# 11_Camera_Input.net
KiCad netlist of a schematic drawn in Altium Designer
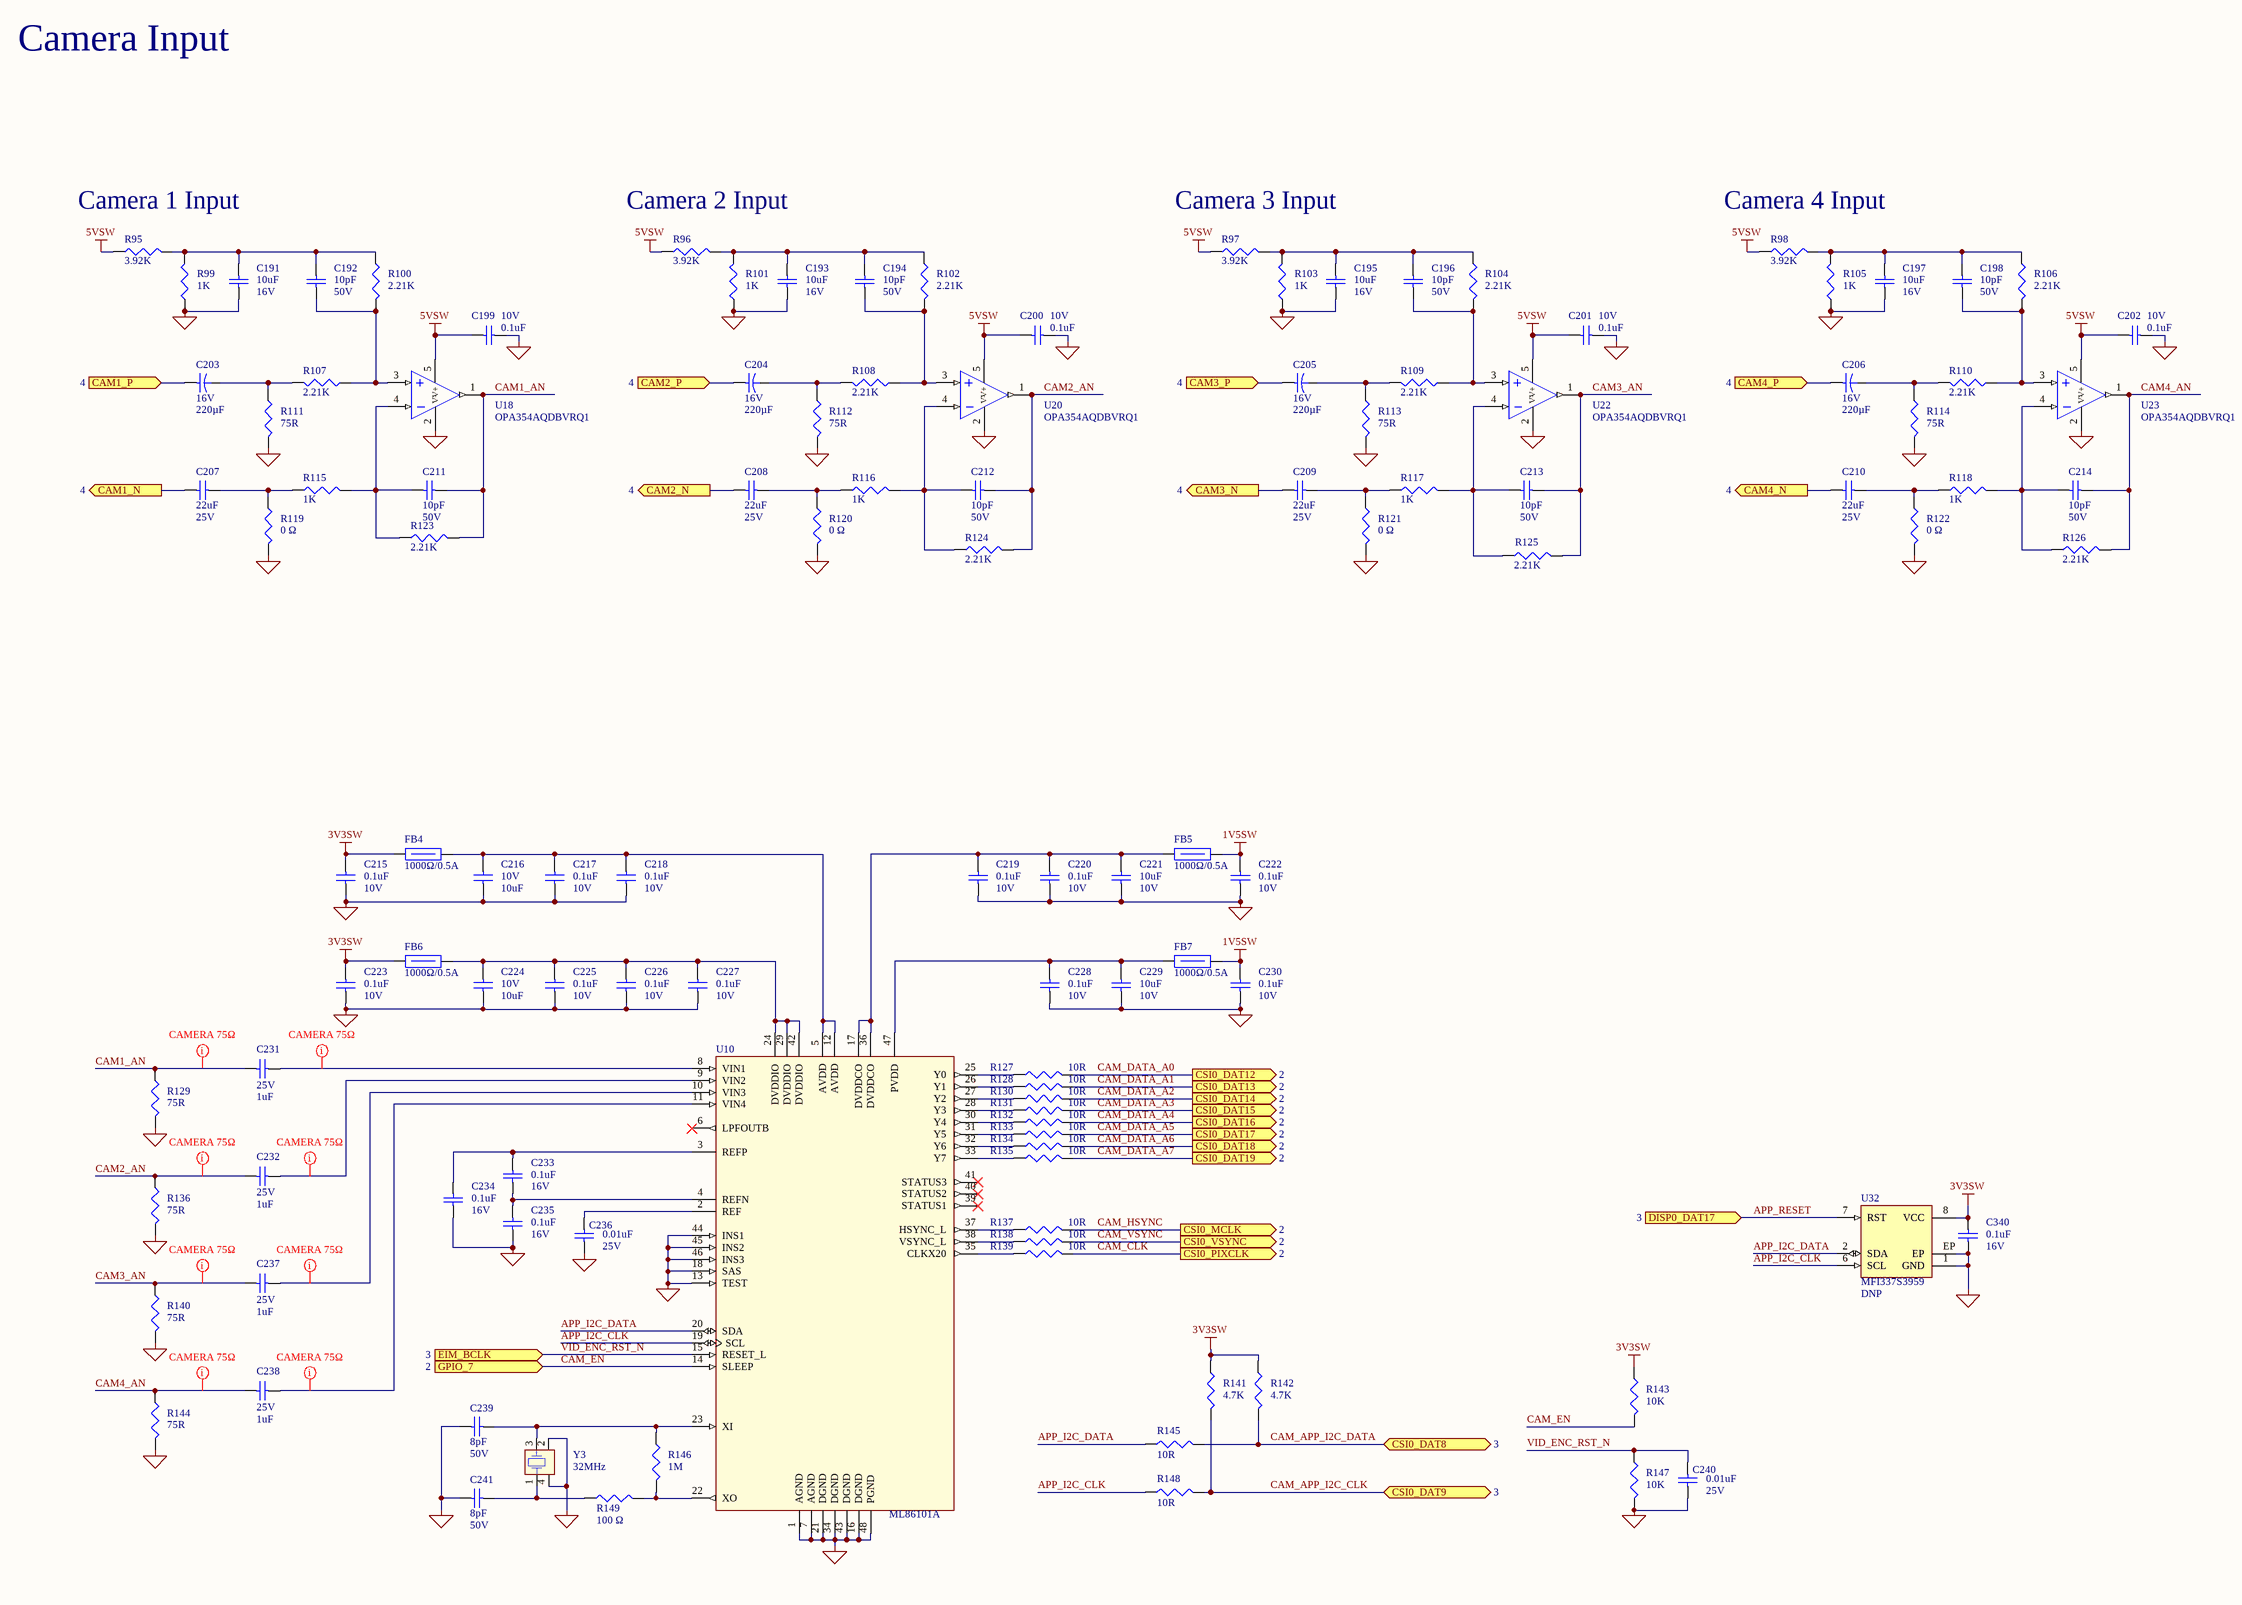
[diagram p0: 11 Camera Input.SchDoc]

(export (version "E")
  (design (tool "Eeschema 10.0.6"))
  (components
    (comp (ref "C191")
      (value "10uF")
      (footprint "CAP_0603")
      (description "Cap, Cer, 10uF, 16V, 20%, X5R, 0603")
      (fields
        (field (name "TOLERANCE") "±20%")
        (field (name "MANUFACTURER") "Murata Electronics North America")
        (field (name "VOLTAGE") "16V")
      )
      (libsource (lib "Firstview") (part "Cap 10uF 16V 0603"))
    )
    (comp (ref "C192")
      (value "10pF")
      (footprint "CAP_0402")
      (description "Cap, Cer, 10pF, 50V, 5%, C0G/NP0, 0402")
      (fields
        (field (name "TOLERANCE") "5%")
        (field (name "MANUFACTURER") "Yageo")
        (field (name "VOLTAGE") "50V")
      )
      (libsource (lib "Firstview") (part "Cap 10pF 50V 0402"))
    )
    (comp (ref "C193")
      (value "10uF")
      (footprint "CAP_0603")
      (description "Cap, Cer, 10uF, 16V, 20%, X5R, 0603")
      (fields
        (field (name "TOLERANCE") "±20%")
        (field (name "MANUFACTURER") "Murata Electronics North America")
        (field (name "VOLTAGE") "16V")
      )
      (libsource (lib "Firstview") (part "Cap 10uF 16V 0603"))
    )
    (comp (ref "C194")
      (value "10pF")
      (footprint "CAP_0402")
      (description "Cap, Cer, 10pF, 50V, 5%, C0G/NP0, 0402")
      (fields
        (field (name "TOLERANCE") "5%")
        (field (name "MANUFACTURER") "Yageo")
        (field (name "VOLTAGE") "50V")
      )
      (libsource (lib "Firstview") (part "Cap 10pF 50V 0402"))
    )
    (comp (ref "C195")
      (value "10uF")
      (footprint "CAP_0603")
      (description "Cap, Cer, 10uF, 16V, 20%, X5R, 0603")
      (fields
        (field (name "TOLERANCE") "±20%")
        (field (name "MANUFACTURER") "Murata Electronics North America")
        (field (name "VOLTAGE") "16V")
      )
      (libsource (lib "Firstview") (part "Cap 10uF 16V 0603"))
    )
    (comp (ref "C196")
      (value "10pF")
      (footprint "CAP_0402")
      (description "Cap, Cer, 10pF, 50V, 5%, C0G/NP0, 0402")
      (fields
        (field (name "TOLERANCE") "5%")
        (field (name "MANUFACTURER") "Yageo")
        (field (name "VOLTAGE") "50V")
      )
      (libsource (lib "Firstview") (part "Cap 10pF 50V 0402"))
    )
    (comp (ref "C197")
      (value "10uF")
      (footprint "CAP_0603")
      (description "Cap, Cer, 10uF, 16V, 20%, X5R, 0603")
      (fields
        (field (name "TOLERANCE") "±20%")
        (field (name "MANUFACTURER") "Murata Electronics North America")
        (field (name "VOLTAGE") "16V")
      )
      (libsource (lib "Firstview") (part "Cap 10uF 16V 0603"))
    )
    (comp (ref "C198")
      (value "10pF")
      (footprint "CAP_0402")
      (description "Cap, Cer, 10pF, 50V, 5%, C0G/NP0, 0402")
      (fields
        (field (name "TOLERANCE") "5%")
        (field (name "MANUFACTURER") "Yageo")
        (field (name "VOLTAGE") "50V")
      )
      (libsource (lib "Firstview") (part "Cap 10pF 50V 0402"))
    )
    (comp (ref "C199")
      (value "0.1uF")
      (footprint "CAP_0402")
      (description "Cap, Cer, 0.1uF, 10V, 10%, X5R, 0402")
      (fields
        (field (name "TOLERANCE") "±10%")
        (field (name "MANUFACTURER") "Murata Electronics North America")
        (field (name "VOLTAGE") "10V")
      )
      (libsource (lib "Firstview") (part "Cap 0.1uF 10V 0402"))
    )
    (comp (ref "C200")
      (value "0.1uF")
      (footprint "CAP_0402")
      (description "Cap, Cer, 0.1uF, 10V, 10%, X5R, 0402")
      (fields
        (field (name "TOLERANCE") "±10%")
        (field (name "MANUFACTURER") "Murata Electronics North America")
        (field (name "VOLTAGE") "10V")
      )
      (libsource (lib "Firstview") (part "Cap 0.1uF 10V 0402"))
    )
    (comp (ref "C201")
      (value "0.1uF")
      (footprint "CAP_0402")
      (description "Cap, Cer, 0.1uF, 10V, 10%, X5R, 0402")
      (fields
        (field (name "TOLERANCE") "±10%")
        (field (name "MANUFACTURER") "Murata Electronics North America")
        (field (name "VOLTAGE") "10V")
      )
      (libsource (lib "Firstview") (part "Cap 0.1uF 10V 0402"))
    )
    (comp (ref "C202")
      (value "0.1uF")
      (footprint "CAP_0402")
      (description "Cap, Cer, 0.1uF, 10V, 10%, X5R, 0402")
      (fields
        (field (name "TOLERANCE") "±10%")
        (field (name "MANUFACTURER") "Murata Electronics North America")
        (field (name "VOLTAGE") "10V")
      )
      (libsource (lib "Firstview") (part "Cap 0.1uF 10V 0402"))
    )
    (comp (ref "C203")
      (value "220µF")
      (footprint "SMD(6.6x6.6)_UWT1C221MCL1GS")
      (description "Cap, Alum, 220µF, 16V, 20%, SMD")
      (fields
        (field (name "TOLERANCE") "20%")
        (field (name "MANUFACTURER") "Nichicon")
        (field (name "VOLTAGE") "16V")
      )
      (libsource (lib "Firstview") (part "Cap 220µF 16V"))
    )
    (comp (ref "C204")
      (value "220µF")
      (footprint "SMD(6.6x6.6)_UWT1C221MCL1GS")
      (description "Cap, Alum, 220µF, 16V, 20%, SMD")
      (fields
        (field (name "TOLERANCE") "20%")
        (field (name "MANUFACTURER") "Nichicon")
        (field (name "VOLTAGE") "16V")
      )
      (libsource (lib "Firstview") (part "Cap 220µF 16V"))
    )
    (comp (ref "C205")
      (value "220µF")
      (footprint "SMD(6.6x6.6)_UWT1C221MCL1GS")
      (description "Cap, Alum, 220µF, 16V, 20%, SMD")
      (fields
        (field (name "TOLERANCE") "20%")
        (field (name "MANUFACTURER") "Nichicon")
        (field (name "VOLTAGE") "16V")
      )
      (libsource (lib "Firstview") (part "Cap 220µF 16V"))
    )
    (comp (ref "C206")
      (value "220µF")
      (footprint "SMD(6.6x6.6)_UWT1C221MCL1GS")
      (description "Cap, Alum, 220µF, 16V, 20%, SMD")
      (fields
        (field (name "TOLERANCE") "20%")
        (field (name "MANUFACTURER") "Nichicon")
        (field (name "VOLTAGE") "16V")
      )
      (libsource (lib "Firstview") (part "Cap 220µF 16V"))
    )
    (comp (ref "C207")
      (value "22uF")
      (footprint "CAP_0805")
      (description "Cap, Cer, 22uF, 25V, 20%, X5R, 0805")
      (fields
        (field (name "TOLERANCE") "±20%")
        (field (name "MANUFACTURER") "Samsung Electro-Mechanics America, Inc")
        (field (name "VOLTAGE") "25V")
      )
      (libsource (lib "Firstview") (part "Cap 22uF 25V 0805"))
    )
    (comp (ref "C208")
      (value "22uF")
      (footprint "CAP_0805")
      (description "Cap, Cer, 22uF, 25V, 20%, X5R, 0805")
      (fields
        (field (name "TOLERANCE") "±20%")
        (field (name "MANUFACTURER") "Samsung Electro-Mechanics America, Inc")
        (field (name "VOLTAGE") "25V")
      )
      (libsource (lib "Firstview") (part "Cap 22uF 25V 0805"))
    )
    (comp (ref "C209")
      (value "22uF")
      (footprint "CAP_0805")
      (description "Cap, Cer, 22uF, 25V, 20%, X5R, 0805")
      (fields
        (field (name "TOLERANCE") "±20%")
        (field (name "MANUFACTURER") "Samsung Electro-Mechanics America, Inc")
        (field (name "VOLTAGE") "25V")
      )
      (libsource (lib "Firstview") (part "Cap 22uF 25V 0805"))
    )
    (comp (ref "C210")
      (value "22uF")
      (footprint "CAP_0805")
      (description "Cap, Cer, 22uF, 25V, 20%, X5R, 0805")
      (fields
        (field (name "TOLERANCE") "±20%")
        (field (name "MANUFACTURER") "Samsung Electro-Mechanics America, Inc")
        (field (name "VOLTAGE") "25V")
      )
      (libsource (lib "Firstview") (part "Cap 22uF 25V 0805"))
    )
    (comp (ref "C211")
      (value "10pF")
      (footprint "CAP_0402")
      (description "Cap, Cer, 10pF, 50V, 5%, C0G/NP0, 0402")
      (fields
        (field (name "TOLERANCE") "5%")
        (field (name "MANUFACTURER") "Yageo")
        (field (name "VOLTAGE") "50V")
      )
      (libsource (lib "Firstview") (part "Cap 10pF 50V 0402"))
    )
    (comp (ref "C212")
      (value "10pF")
      (footprint "CAP_0402")
      (description "Cap, Cer, 10pF, 50V, 5%, C0G/NP0, 0402")
      (fields
        (field (name "TOLERANCE") "5%")
        (field (name "MANUFACTURER") "Yageo")
        (field (name "VOLTAGE") "50V")
      )
      (libsource (lib "Firstview") (part "Cap 10pF 50V 0402"))
    )
    (comp (ref "C213")
      (value "10pF")
      (footprint "CAP_0402")
      (description "Cap, Cer, 10pF, 50V, 5%, C0G/NP0, 0402")
      (fields
        (field (name "TOLERANCE") "5%")
        (field (name "MANUFACTURER") "Yageo")
        (field (name "VOLTAGE") "50V")
      )
      (libsource (lib "Firstview") (part "Cap 10pF 50V 0402"))
    )
    (comp (ref "C214")
      (value "10pF")
      (footprint "CAP_0402")
      (description "Cap, Cer, 10pF, 50V, 5%, C0G/NP0, 0402")
      (fields
        (field (name "TOLERANCE") "5%")
        (field (name "MANUFACTURER") "Yageo")
        (field (name "VOLTAGE") "50V")
      )
      (libsource (lib "Firstview") (part "Cap 10pF 50V 0402"))
    )
    (comp (ref "C215")
      (value "0.1uF")
      (footprint "CAP_0402")
      (description "Cap, Cer, 0.1uF, 10V, 10%, X5R, 0402")
      (fields
        (field (name "TOLERANCE") "±10%")
        (field (name "MANUFACTURER") "Murata Electronics North America")
        (field (name "VOLTAGE") "10V")
      )
      (libsource (lib "Firstview") (part "Cap 0.1uF 10V 0402"))
    )
    (comp (ref "C216")
      (value "10uF")
      (footprint "CAP_0603")
      (description "Cap, Cer, 10uF, 10V, 10%, X5R, 0603")
      (fields
        (field (name "TOLERANCE") "±10%")
        (field (name "VOLTAGE") "10V")
        (field (name "MANUFACTURER") "TDK Corporation")
      )
      (libsource (lib "Firstview") (part "Cap 10uF 10V 0603"))
    )
    (comp (ref "C217")
      (value "0.1uF")
      (footprint "CAP_0402")
      (description "Cap, Cer, 0.1uF, 10V, 10%, X5R, 0402")
      (fields
        (field (name "TOLERANCE") "±10%")
        (field (name "MANUFACTURER") "Murata Electronics North America")
        (field (name "VOLTAGE") "10V")
      )
      (libsource (lib "Firstview") (part "Cap 0.1uF 10V 0402"))
    )
    (comp (ref "C218")
      (value "0.1uF")
      (footprint "CAP_0402")
      (description "Cap, Cer, 0.1uF, 10V, 10%, X5R, 0402")
      (fields
        (field (name "TOLERANCE") "±10%")
        (field (name "MANUFACTURER") "Murata Electronics North America")
        (field (name "VOLTAGE") "10V")
      )
      (libsource (lib "Firstview") (part "Cap 0.1uF 10V 0402"))
    )
    (comp (ref "C219")
      (value "0.1uF")
      (footprint "CAP_0402")
      (description "Cap, Cer, 0.1uF, 10V, 10%, X5R, 0402")
      (fields
        (field (name "TOLERANCE") "±10%")
        (field (name "MANUFACTURER") "Murata Electronics North America")
        (field (name "VOLTAGE") "10V")
      )
      (libsource (lib "Firstview") (part "Cap 0.1uF 10V 0402"))
    )
    (comp (ref "C220")
      (value "0.1uF")
      (footprint "CAP_0402")
      (description "Cap, Cer, 0.1uF, 10V, 10%, X5R, 0402")
      (fields
        (field (name "TOLERANCE") "±10%")
        (field (name "MANUFACTURER") "Murata Electronics North America")
        (field (name "VOLTAGE") "10V")
      )
      (libsource (lib "Firstview") (part "Cap 0.1uF 10V 0402"))
    )
    (comp (ref "C221")
      (value "10uF")
      (footprint "CAP_0603")
      (description "Cap, Cer, 10uF, 10V, 10%, X5R, 0603")
      (fields
        (field (name "TOLERANCE") "±10%")
        (field (name "VOLTAGE") "10V")
        (field (name "MANUFACTURER") "TDK Corporation")
      )
      (libsource (lib "Firstview") (part "Cap 10uF 10V 0603"))
    )
    (comp (ref "C222")
      (value "0.1uF")
      (footprint "CAP_0402")
      (description "Cap, Cer, 0.1uF, 10V, 10%, X5R, 0402")
      (fields
        (field (name "TOLERANCE") "±10%")
        (field (name "MANUFACTURER") "Murata Electronics North America")
        (field (name "VOLTAGE") "10V")
      )
      (libsource (lib "Firstview") (part "Cap 0.1uF 10V 0402"))
    )
    (comp (ref "C223")
      (value "0.1uF")
      (footprint "CAP_0402")
      (description "Cap, Cer, 0.1uF, 10V, 10%, X5R, 0402")
      (fields
        (field (name "TOLERANCE") "±10%")
        (field (name "MANUFACTURER") "Murata Electronics North America")
        (field (name "VOLTAGE") "10V")
      )
      (libsource (lib "Firstview") (part "Cap 0.1uF 10V 0402"))
    )
    (comp (ref "C224")
      (value "10uF")
      (footprint "CAP_0603")
      (description "Cap, Cer, 10uF, 10V, 10%, X5R, 0603")
      (fields
        (field (name "TOLERANCE") "±10%")
        (field (name "VOLTAGE") "10V")
        (field (name "MANUFACTURER") "TDK Corporation")
      )
      (libsource (lib "Firstview") (part "Cap 10uF 10V 0603"))
    )
    (comp (ref "C225")
      (value "0.1uF")
      (footprint "CAP_0402")
      (description "Cap, Cer, 0.1uF, 10V, 10%, X5R, 0402")
      (fields
        (field (name "TOLERANCE") "±10%")
        (field (name "MANUFACTURER") "Murata Electronics North America")
        (field (name "VOLTAGE") "10V")
      )
      (libsource (lib "Firstview") (part "Cap 0.1uF 10V 0402"))
    )
    (comp (ref "C226")
      (value "0.1uF")
      (footprint "CAP_0402")
      (description "Cap, Cer, 0.1uF, 10V, 10%, X5R, 0402")
      (fields
        (field (name "TOLERANCE") "±10%")
        (field (name "MANUFACTURER") "Murata Electronics North America")
        (field (name "VOLTAGE") "10V")
      )
      (libsource (lib "Firstview") (part "Cap 0.1uF 10V 0402"))
    )
    (comp (ref "C227")
      (value "0.1uF")
      (footprint "CAP_0402")
      (description "Cap, Cer, 0.1uF, 10V, 10%, X5R, 0402")
      (fields
        (field (name "TOLERANCE") "±10%")
        (field (name "MANUFACTURER") "Murata Electronics North America")
        (field (name "VOLTAGE") "10V")
      )
      (libsource (lib "Firstview") (part "Cap 0.1uF 10V 0402"))
    )
    (comp (ref "C228")
      (value "0.1uF")
      (footprint "CAP_0402")
      (description "Cap, Cer, 0.1uF, 10V, 10%, X5R, 0402")
      (fields
        (field (name "TOLERANCE") "±10%")
        (field (name "MANUFACTURER") "Murata Electronics North America")
        (field (name "VOLTAGE") "10V")
      )
      (libsource (lib "Firstview") (part "Cap 0.1uF 10V 0402"))
    )
    (comp (ref "C229")
      (value "10uF")
      (footprint "CAP_0603")
      (description "Cap, Cer, 10uF, 10V, 10%, X5R, 0603")
      (fields
        (field (name "TOLERANCE") "±10%")
        (field (name "VOLTAGE") "10V")
        (field (name "MANUFACTURER") "TDK Corporation")
      )
      (libsource (lib "Firstview") (part "Cap 10uF 10V 0603"))
    )
    (comp (ref "C230")
      (value "0.1uF")
      (footprint "CAP_0402")
      (description "Cap, Cer, 0.1uF, 10V, 10%, X5R, 0402")
      (fields
        (field (name "TOLERANCE") "±10%")
        (field (name "MANUFACTURER") "Murata Electronics North America")
        (field (name "VOLTAGE") "10V")
      )
      (libsource (lib "Firstview") (part "Cap 0.1uF 10V 0402"))
    )
    (comp (ref "C231")
      (value "1uF")
      (footprint "CAP_0402")
      (description "Cap, Cer, 1uF, 25V, 10%, X5R, 0402")
      (fields
        (field (name "MANUFACTURER") "Taiyo Yuden")
        (field (name "VOLTAGE") "25V")
        (field (name "Comment") "Cap 1uF 25V 0402")
      )
      (libsource (lib "Firstview") (part "Cap 1uF 25V 0402"))
    )
    (comp (ref "C232")
      (value "1uF")
      (footprint "CAP_0402")
      (description "Cap, Cer, 1uF, 25V, 10%, X5R, 0402")
      (fields
        (field (name "MANUFACTURER") "Taiyo Yuden")
        (field (name "VOLTAGE") "25V")
        (field (name "Comment") "Cap 1uF 25V 0402")
      )
      (libsource (lib "Firstview") (part "Cap 1uF 25V 0402"))
    )
    (comp (ref "C233")
      (value "0.1uF")
      (footprint "CAP_0402")
      (description "Cap, Cer, 0.1uF, 16V, 10%, X7R, 0402")
      (fields
        (field (name "TOLERANCE") "±10%")
        (field (name "MANUFACTURER") "Murata Electronics North America")
        (field (name "VOLTAGE") "16V")
      )
      (libsource (lib "Firstview") (part "Cap 0.1uF 16V 0402"))
    )
    (comp (ref "C234")
      (value "0.1uF")
      (footprint "CAP_0402")
      (description "Cap, Cer, 0.1uF, 16V, 10%, X7R, 0402")
      (fields
        (field (name "TOLERANCE") "±10%")
        (field (name "MANUFACTURER") "Murata Electronics North America")
        (field (name "VOLTAGE") "16V")
      )
      (libsource (lib "Firstview") (part "Cap 0.1uF 16V 0402"))
    )
    (comp (ref "C235")
      (value "0.1uF")
      (footprint "CAP_0402")
      (description "Cap, Cer, 0.1uF, 16V, 10%, X7R, 0402")
      (fields
        (field (name "TOLERANCE") "±10%")
        (field (name "MANUFACTURER") "Murata Electronics North America")
        (field (name "VOLTAGE") "16V")
      )
      (libsource (lib "Firstview") (part "Cap 0.1uF 16V 0402"))
    )
    (comp (ref "C236")
      (value "0.01uF")
      (footprint "CAP_0402")
      (description "Cap, Cer, 0.01uF, 25V, ±10%, X7R, 0402")
      (fields
        (field (name "TOLERANCE") "±10%")
        (field (name "MANUFACTURER") "Murata")
        (field (name "VOLTAGE") "25V")
      )
      (libsource (lib "Firstview") (part "Cap 0.01uF 50V 0402"))
    )
    (comp (ref "C237")
      (value "1uF")
      (footprint "CAP_0402")
      (description "Cap, Cer, 1uF, 25V, 10%, X5R, 0402")
      (fields
        (field (name "MANUFACTURER") "Taiyo Yuden")
        (field (name "VOLTAGE") "25V")
        (field (name "Comment") "Cap 1uF 25V 0402")
      )
      (libsource (lib "Firstview") (part "Cap 1uF 25V 0402"))
    )
    (comp (ref "C238")
      (value "1uF")
      (footprint "CAP_0402")
      (description "Cap, Cer, 1uF, 25V, 10%, X5R, 0402")
      (fields
        (field (name "MANUFACTURER") "Taiyo Yuden")
        (field (name "VOLTAGE") "25V")
        (field (name "Comment") "Cap 1uF 25V 0402")
      )
      (libsource (lib "Firstview") (part "Cap 1uF 25V 0402"))
    )
    (comp (ref "C239")
      (value "8pF")
      (footprint "CAP_0402")
      (description "Cap, Cer, 8pF, 50V, ±0.5pF, C0G/NP0, 0402")
      (fields
        (field (name "TOLERANCE") "±0.5pF")
        (field (name "MANUFACTURER") "Murata Electronics North America")
        (field (name "VOLTAGE") "50V")
      )
      (libsource (lib "Firstview") (part "Cap 8pF 50V 0402"))
    )
    (comp (ref "C240")
      (value "0.01uF")
      (footprint "CAP_0402")
      (description "Cap, Cer, 0.01uF, 25V, ±10%, X7R, 0402")
      (fields
        (field (name "TOLERANCE") "±10%")
        (field (name "MANUFACTURER") "Murata")
        (field (name "VOLTAGE") "25V")
      )
      (libsource (lib "Firstview") (part "Cap 0.01uF 50V 0402"))
    )
    (comp (ref "C241")
      (value "8pF")
      (footprint "CAP_0402")
      (description "Cap, Cer, 8pF, 50V, ±0.5pF, C0G/NP0, 0402")
      (fields
        (field (name "TOLERANCE") "±0.5pF")
        (field (name "MANUFACTURER") "Murata Electronics North America")
        (field (name "VOLTAGE") "50V")
      )
      (libsource (lib "Firstview") (part "Cap 8pF 50V 0402"))
    )
    (comp (ref "C340")
      (value "0.1uF")
      (footprint "CAP_0402")
      (description "Cap, Cer, 0.1uF, 16V, 10%, X7R, 0402")
      (fields
        (field (name "TOLERANCE") "±10%")
        (field (name "MANUFACTURER") "Murata Electronics North America")
        (field (name "VOLTAGE") "16V")
      )
      (libsource (lib "Firstview") (part "Cap 0.1uF 16V 0402"))
    )
    (comp (ref "FB4")
      (value "1000Ω/0.5A")
      (footprint "IND_0805")
      (description "Ind, Ferrite Bead, 1000R, 0.5A, 400mOhm, 0805")
      (fields
        (field (name "MANUFACTURER") "Pulse Electronics Corporation")
        (field (name "Comment") "PE-0805FB102ST")
      )
      (libsource (lib "Firstview") (part "PE-0805FB102ST"))
    )
    (comp (ref "FB5")
      (value "1000Ω/0.5A")
      (footprint "IND_0805")
      (description "Ind, Ferrite Bead, 1000R, 0.5A, 400mOhm, 0805")
      (fields
        (field (name "MANUFACTURER") "Pulse Electronics Corporation")
        (field (name "Comment") "PE-0805FB102ST")
      )
      (libsource (lib "Firstview") (part "PE-0805FB102ST"))
    )
    (comp (ref "FB6")
      (value "1000Ω/0.5A")
      (footprint "IND_0805")
      (description "Ind, Ferrite Bead, 1000R, 0.5A, 400mOhm, 0805")
      (fields
        (field (name "MANUFACTURER") "Pulse Electronics Corporation")
        (field (name "Comment") "PE-0805FB102ST")
      )
      (libsource (lib "Firstview") (part "PE-0805FB102ST"))
    )
    (comp (ref "FB7")
      (value "1000Ω/0.5A")
      (footprint "IND_0805")
      (description "Ind, Ferrite Bead, 1000R, 0.5A, 400mOhm, 0805")
      (fields
        (field (name "MANUFACTURER") "Pulse Electronics Corporation")
        (field (name "Comment") "PE-0805FB102ST")
      )
      (libsource (lib "Firstview") (part "PE-0805FB102ST"))
    )
    (comp (ref "R95")
      (value "3.92K")
      (footprint "RES_0402")
      (description "Res, 3.92K, 0.063W, 1%, 0402")
      (fields (field (name "TOLERANCE") "1%") (field (name "MANUFACTURER") "Rohm Semiconductor"))
      (libsource (lib "Firstview") (part "Res 3.92K 0.063W"))
    )
    (comp (ref "R96")
      (value "3.92K")
      (footprint "RES_0402")
      (description "Res, 3.92K, 0.063W, 1%, 0402")
      (fields (field (name "TOLERANCE") "1%") (field (name "MANUFACTURER") "Rohm Semiconductor"))
      (libsource (lib "Firstview") (part "Res 3.92K 0.063W"))
    )
    (comp (ref "R97")
      (value "3.92K")
      (footprint "RES_0402")
      (description "Res, 3.92K, 0.063W, 1%, 0402")
      (fields (field (name "TOLERANCE") "1%") (field (name "MANUFACTURER") "Rohm Semiconductor"))
      (libsource (lib "Firstview") (part "Res 3.92K 0.063W"))
    )
    (comp (ref "R98")
      (value "3.92K")
      (footprint "RES_0402")
      (description "Res, 3.92K, 0.063W, 1%, 0402")
      (fields (field (name "TOLERANCE") "1%") (field (name "MANUFACTURER") "Rohm Semiconductor"))
      (libsource (lib "Firstview") (part "Res 3.92K 0.063W"))
    )
    (comp (ref "R99")
      (value "1K")
      (footprint "RES_0402")
      (description "Res, 1K, 0.063W, 1%, 0402")
      (fields (field (name "TOLERANCE") "±1%") (field (name "MANUFACTURER") "Vishay Dale"))
      (libsource (lib "Firstview") (part "Res 1K 0.063W"))
    )
    (comp (ref "R100")
      (value "2.21K")
      (footprint "RES_0402")
      (description "Res, 2.21K, 0.063W, 1%, 0402")
      (fields (field (name "TOLERANCE") "1%") (field (name "MANUFACTURER") "Yageo"))
      (libsource (lib "Firstview") (part "Res 2.21K 0.063W"))
    )
    (comp (ref "R101")
      (value "1K")
      (footprint "RES_0402")
      (description "Res, 1K, 0.063W, 1%, 0402")
      (fields (field (name "TOLERANCE") "±1%") (field (name "MANUFACTURER") "Vishay Dale"))
      (libsource (lib "Firstview") (part "Res 1K 0.063W"))
    )
    (comp (ref "R102")
      (value "2.21K")
      (footprint "RES_0402")
      (description "Res, 2.21K, 0.063W, 1%, 0402")
      (fields (field (name "TOLERANCE") "1%") (field (name "MANUFACTURER") "Yageo"))
      (libsource (lib "Firstview") (part "Res 2.21K 0.063W"))
    )
    (comp (ref "R103")
      (value "1K")
      (footprint "RES_0402")
      (description "Res, 1K, 0.063W, 1%, 0402")
      (fields (field (name "TOLERANCE") "±1%") (field (name "MANUFACTURER") "Vishay Dale"))
      (libsource (lib "Firstview") (part "Res 1K 0.063W"))
    )
    (comp (ref "R104")
      (value "2.21K")
      (footprint "RES_0402")
      (description "Res, 2.21K, 0.063W, 1%, 0402")
      (fields (field (name "TOLERANCE") "1%") (field (name "MANUFACTURER") "Yageo"))
      (libsource (lib "Firstview") (part "Res 2.21K 0.063W"))
    )
    (comp (ref "R105")
      (value "1K")
      (footprint "RES_0402")
      (description "Res, 1K, 0.063W, 1%, 0402")
      (fields (field (name "TOLERANCE") "±1%") (field (name "MANUFACTURER") "Vishay Dale"))
      (libsource (lib "Firstview") (part "Res 1K 0.063W"))
    )
    (comp (ref "R106")
      (value "2.21K")
      (footprint "RES_0402")
      (description "Res, 2.21K, 0.063W, 1%, 0402")
      (fields (field (name "TOLERANCE") "1%") (field (name "MANUFACTURER") "Yageo"))
      (libsource (lib "Firstview") (part "Res 2.21K 0.063W"))
    )
    (comp (ref "R107")
      (value "2.21K")
      (footprint "RES_0402")
      (description "Res, 2.21K, 0.063W, 1%, 0402")
      (fields (field (name "TOLERANCE") "1%") (field (name "MANUFACTURER") "Yageo"))
      (libsource (lib "Firstview") (part "Res 2.21K 0.063W"))
    )
    (comp (ref "R108")
      (value "2.21K")
      (footprint "RES_0402")
      (description "Res, 2.21K, 0.063W, 1%, 0402")
      (fields (field (name "TOLERANCE") "1%") (field (name "MANUFACTURER") "Yageo"))
      (libsource (lib "Firstview") (part "Res 2.21K 0.063W"))
    )
    (comp (ref "R109")
      (value "2.21K")
      (footprint "RES_0402")
      (description "Res, 2.21K, 0.063W, 1%, 0402")
      (fields (field (name "TOLERANCE") "1%") (field (name "MANUFACTURER") "Yageo"))
      (libsource (lib "Firstview") (part "Res 2.21K 0.063W"))
    )
    (comp (ref "R110")
      (value "2.21K")
      (footprint "RES_0402")
      (description "Res, 2.21K, 0.063W, 1%, 0402")
      (fields (field (name "TOLERANCE") "1%") (field (name "MANUFACTURER") "Yageo"))
      (libsource (lib "Firstview") (part "Res 2.21K 0.063W"))
    )
    (comp (ref "R111")
      (value "75R")
      (footprint "RES_0402")
      (description "Res, 2.21K, 0.063W, 1%, 0402")
      (fields (field (name "TOLERANCE") "1%") (field (name "MANUFACTURER") "Rohm Semiconductor"))
      (libsource (lib "Firstview") (part "Res 75R 0.063W"))
    )
    (comp (ref "R112")
      (value "75R")
      (footprint "RES_0402")
      (description "Res, 2.21K, 0.063W, 1%, 0402")
      (fields (field (name "TOLERANCE") "1%") (field (name "MANUFACTURER") "Rohm Semiconductor"))
      (libsource (lib "Firstview") (part "Res 75R 0.063W"))
    )
    (comp (ref "R113")
      (value "75R")
      (footprint "RES_0402")
      (description "Res, 2.21K, 0.063W, 1%, 0402")
      (fields (field (name "TOLERANCE") "1%") (field (name "MANUFACTURER") "Rohm Semiconductor"))
      (libsource (lib "Firstview") (part "Res 75R 0.063W"))
    )
    (comp (ref "R114")
      (value "75R")
      (footprint "RES_0402")
      (description "Res, 2.21K, 0.063W, 1%, 0402")
      (fields (field (name "TOLERANCE") "1%") (field (name "MANUFACTURER") "Rohm Semiconductor"))
      (libsource (lib "Firstview") (part "Res 75R 0.063W"))
    )
    (comp (ref "R115")
      (value "1K")
      (footprint "RES_0402")
      (description "Res, 1K, 0.063W, 1%, 0402")
      (fields (field (name "TOLERANCE") "±1%") (field (name "MANUFACTURER") "Vishay Dale"))
      (libsource (lib "Firstview") (part "Res 1K 0.063W"))
    )
    (comp (ref "R116")
      (value "1K")
      (footprint "RES_0402")
      (description "Res, 1K, 0.063W, 1%, 0402")
      (fields (field (name "TOLERANCE") "±1%") (field (name "MANUFACTURER") "Vishay Dale"))
      (libsource (lib "Firstview") (part "Res 1K 0.063W"))
    )
    (comp (ref "R117")
      (value "1K")
      (footprint "RES_0402")
      (description "Res, 1K, 0.063W, 1%, 0402")
      (fields (field (name "TOLERANCE") "±1%") (field (name "MANUFACTURER") "Vishay Dale"))
      (libsource (lib "Firstview") (part "Res 1K 0.063W"))
    )
    (comp (ref "R118")
      (value "1K")
      (footprint "RES_0402")
      (description "Res, 1K, 0.063W, 1%, 0402")
      (fields (field (name "TOLERANCE") "±1%") (field (name "MANUFACTURER") "Vishay Dale"))
      (libsource (lib "Firstview") (part "Res 1K 0.063W"))
    )
    (comp (ref "R119")
      (value "0 Ω")
      (footprint "RES_0402")
      (description "Res, 0 ohm, 1/16W, 0402")
      (fields (field (name "MANUFACTURER") "Vishay Dale") (field (name "Comment") "Res 0 ohm 0.1W"))
      (libsource (lib "Firstview") (part "Res 0 ohm 0.1W"))
    )
    (comp (ref "R120")
      (value "0 Ω")
      (footprint "RES_0402")
      (description "Res, 0 ohm, 1/16W, 0402")
      (fields (field (name "MANUFACTURER") "Vishay Dale") (field (name "Comment") "Res 0 ohm 0.1W"))
      (libsource (lib "Firstview") (part "Res 0 ohm 0.1W"))
    )
    (comp (ref "R121")
      (value "0 Ω")
      (footprint "RES_0402")
      (description "Res, 0 ohm, 1/16W, 0402")
      (fields (field (name "MANUFACTURER") "Vishay Dale") (field (name "Comment") "Res 0 ohm 0.1W"))
      (libsource (lib "Firstview") (part "Res 0 ohm 0.1W"))
    )
    (comp (ref "R122")
      (value "0 Ω")
      (footprint "RES_0402")
      (description "Res, 0 ohm, 1/16W, 0402")
      (fields (field (name "MANUFACTURER") "Vishay Dale") (field (name "Comment") "Res 0 ohm 0.1W"))
      (libsource (lib "Firstview") (part "Res 0 ohm 0.1W"))
    )
    (comp (ref "R123")
      (value "2.21K")
      (footprint "RES_0402")
      (description "Res, 2.21K, 0.063W, 1%, 0402")
      (fields (field (name "TOLERANCE") "1%") (field (name "MANUFACTURER") "Yageo"))
      (libsource (lib "Firstview") (part "Res 2.21K 0.063W"))
    )
    (comp (ref "R124")
      (value "2.21K")
      (footprint "RES_0402")
      (description "Res, 2.21K, 0.063W, 1%, 0402")
      (fields (field (name "TOLERANCE") "1%") (field (name "MANUFACTURER") "Yageo"))
      (libsource (lib "Firstview") (part "Res 2.21K 0.063W"))
    )
    (comp (ref "R125")
      (value "2.21K")
      (footprint "RES_0402")
      (description "Res, 2.21K, 0.063W, 1%, 0402")
      (fields (field (name "TOLERANCE") "1%") (field (name "MANUFACTURER") "Yageo"))
      (libsource (lib "Firstview") (part "Res 2.21K 0.063W"))
    )
    (comp (ref "R126")
      (value "2.21K")
      (footprint "RES_0402")
      (description "Res, 2.21K, 0.063W, 1%, 0402")
      (fields (field (name "TOLERANCE") "1%") (field (name "MANUFACTURER") "Yageo"))
      (libsource (lib "Firstview") (part "Res 2.21K 0.063W"))
    )
    (comp (ref "R127")
      (value "10R")
      (footprint "RES_0402")
      (description "Res, 10R, 0.1W, 0402")
      (fields
        (field (name "MANUFACTURER") "Panasonic Electronic Components")
        (field (name "Comment") "Res 10R 0.1W")
      )
      (libsource (lib "Firstview") (part "Res 10R 0.1W"))
    )
    (comp (ref "R128")
      (value "10R")
      (footprint "RES_0402")
      (description "Res, 10R, 0.1W, 0402")
      (fields
        (field (name "MANUFACTURER") "Panasonic Electronic Components")
        (field (name "Comment") "Res 10R 0.1W")
      )
      (libsource (lib "Firstview") (part "Res 10R 0.1W"))
    )
    (comp (ref "R129")
      (value "75R")
      (footprint "RES_0402")
      (description "Res, 2.21K, 0.063W, 1%, 0402")
      (fields (field (name "TOLERANCE") "1%") (field (name "MANUFACTURER") "Rohm Semiconductor"))
      (libsource (lib "Firstview") (part "Res 75R 0.063W"))
    )
    (comp (ref "R130")
      (value "10R")
      (footprint "RES_0402")
      (description "Res, 10R, 0.1W, 0402")
      (fields
        (field (name "MANUFACTURER") "Panasonic Electronic Components")
        (field (name "Comment") "Res 10R 0.1W")
      )
      (libsource (lib "Firstview") (part "Res 10R 0.1W"))
    )
    (comp (ref "R131")
      (value "10R")
      (footprint "RES_0402")
      (description "Res, 10R, 0.1W, 0402")
      (fields
        (field (name "MANUFACTURER") "Panasonic Electronic Components")
        (field (name "Comment") "Res 10R 0.1W")
      )
      (libsource (lib "Firstview") (part "Res 10R 0.1W"))
    )
    (comp (ref "R132")
      (value "10R")
      (footprint "RES_0402")
      (description "Res, 10R, 0.1W, 0402")
      (fields
        (field (name "MANUFACTURER") "Panasonic Electronic Components")
        (field (name "Comment") "Res 10R 0.1W")
      )
      (libsource (lib "Firstview") (part "Res 10R 0.1W"))
    )
    (comp (ref "R133")
      (value "10R")
      (footprint "RES_0402")
      (description "Res, 10R, 0.1W, 0402")
      (fields
        (field (name "MANUFACTURER") "Panasonic Electronic Components")
        (field (name "Comment") "Res 10R 0.1W")
      )
      (libsource (lib "Firstview") (part "Res 10R 0.1W"))
    )
    (comp (ref "R134")
      (value "10R")
      (footprint "RES_0402")
      (description "Res, 10R, 0.1W, 0402")
      (fields
        (field (name "MANUFACTURER") "Panasonic Electronic Components")
        (field (name "Comment") "Res 10R 0.1W")
      )
      (libsource (lib "Firstview") (part "Res 10R 0.1W"))
    )
    (comp (ref "R135")
      (value "10R")
      (footprint "RES_0402")
      (description "Res, 10R, 0.1W, 0402")
      (fields
        (field (name "MANUFACTURER") "Panasonic Electronic Components")
        (field (name "Comment") "Res 10R 0.1W")
      )
      (libsource (lib "Firstview") (part "Res 10R 0.1W"))
    )
    (comp (ref "R136")
      (value "75R")
      (footprint "RES_0402")
      (description "Res, 2.21K, 0.063W, 1%, 0402")
      (fields (field (name "TOLERANCE") "1%") (field (name "MANUFACTURER") "Rohm Semiconductor"))
      (libsource (lib "Firstview") (part "Res 75R 0.063W"))
    )
    (comp (ref "R137")
      (value "10R")
      (footprint "RES_0402")
      (description "Res, 10R, 0.1W, 0402")
      (fields
        (field (name "MANUFACTURER") "Panasonic Electronic Components")
        (field (name "Comment") "Res 10R 0.1W")
      )
      (libsource (lib "Firstview") (part "Res 10R 0.1W"))
    )
    (comp (ref "R138")
      (value "10R")
      (footprint "RES_0402")
      (description "Res, 10R, 0.1W, 0402")
      (fields
        (field (name "MANUFACTURER") "Panasonic Electronic Components")
        (field (name "Comment") "Res 10R 0.1W")
      )
      (libsource (lib "Firstview") (part "Res 10R 0.1W"))
    )
    (comp (ref "R139")
      (value "10R")
      (footprint "RES_0402")
      (description "Res, 10R, 0.1W, 0402")
      (fields
        (field (name "MANUFACTURER") "Panasonic Electronic Components")
        (field (name "Comment") "Res 10R 0.1W")
      )
      (libsource (lib "Firstview") (part "Res 10R 0.1W"))
    )
    (comp (ref "R140")
      (value "75R")
      (footprint "RES_0402")
      (description "Res, 2.21K, 0.063W, 1%, 0402")
      (fields (field (name "TOLERANCE") "1%") (field (name "MANUFACTURER") "Rohm Semiconductor"))
      (libsource (lib "Firstview") (part "Res 75R 0.063W"))
    )
    (comp (ref "R141")
      (value "4.7K")
      (footprint "RES_0402")
      (description "Res, 4.70K, 0.063W, 1%, 0402")
      (fields (field (name "MANUFACTURER") "Vishay Dale") (field (name "Comment") "Res 4.7K 0.063W"))
      (libsource (lib "Firstview") (part "Res 4.7K 0.063W"))
    )
    (comp (ref "R142")
      (value "4.7K")
      (footprint "RES_0402")
      (description "Res, 4.70K, 0.063W, 1%, 0402")
      (fields (field (name "MANUFACTURER") "Vishay Dale") (field (name "Comment") "Res 4.7K 0.063W"))
      (libsource (lib "Firstview") (part "Res 4.7K 0.063W"))
    )
    (comp (ref "R143")
      (value "10K")
      (footprint "RES_0402")
      (description "Res, 10K, 1/16W, 1%, 0402")
      (fields (field (name "MANUFACTURER") "Yageo") (field (name "Comment") "Res 10K 0.063W"))
      (libsource (lib "Firstview") (part "Res 10K 0.063W"))
    )
    (comp (ref "R144")
      (value "75R")
      (footprint "RES_0402")
      (description "Res, 2.21K, 0.063W, 1%, 0402")
      (fields (field (name "TOLERANCE") "1%") (field (name "MANUFACTURER") "Rohm Semiconductor"))
      (libsource (lib "Firstview") (part "Res 75R 0.063W"))
    )
    (comp (ref "R145")
      (value "10R")
      (footprint "RES_0402")
      (description "Res, 10R, 0.1W, 0402")
      (fields
        (field (name "MANUFACTURER") "Panasonic Electronic Components")
        (field (name "Comment") "Res 10R 0.1W")
      )
      (libsource (lib "Firstview") (part "Res 10R 0.1W"))
    )
    (comp (ref "R146")
      (value "1M")
      (footprint "RES_0402")
      (description "Res, 1M, 0.063W, 1%, 0402")
      (fields (field (name "MANUFACTURER") "Yageo") (field (name "Comment") "Res 1M 0.063W"))
      (libsource (lib "Firstview") (part "Res 1M 0.063W"))
    )
    (comp (ref "R147")
      (value "10K")
      (footprint "RES_0402")
      (description "Res, 10K, 1/16W, 1%, 0402")
      (fields (field (name "MANUFACTURER") "Yageo") (field (name "Comment") "Res 10K 0.063W"))
      (libsource (lib "Firstview") (part "Res 10K 0.063W"))
    )
    (comp (ref "R148")
      (value "10R")
      (footprint "RES_0402")
      (description "Res, 10R, 0.1W, 0402")
      (fields
        (field (name "MANUFACTURER") "Panasonic Electronic Components")
        (field (name "Comment") "Res 10R 0.1W")
      )
      (libsource (lib "Firstview") (part "Res 10R 0.1W"))
    )
    (comp (ref "R149")
      (value "100 Ω")
      (footprint "RES_0402")
      (description "Res, 100R, 0.063W, 1%, 0402")
      (fields
        (field (name "MANUFACTURER") "Murata Electronics North America")
        (field (name "Comment") "Res 100R 0.063W")
      )
      (libsource (lib "Firstview") (part "Res 100R 0.063W"))
    )
    (comp (ref "U10")
      (value "ML86101A")
      (footprint "TQFP-48_ML86101A")
      (description "IC, Video Decoder, I2C, 4-composite/2-S-video input, TQFP-48")
      (fields (field (name "MANUFACTURER") "Lapis Semiconductor"))
      (libsource (lib "Firstview") (part "ML86101A"))
    )
    (comp (ref "U18")
      (value "OPA354AQDBVRQ1")
      (footprint "SOT-23-5_OPA354A-Q1")
      (description "IC, OpAmp, 250MHz, R-R I/O, SOT-23-5")
      (fields (field (name "MANUFACTURER") "Texas Instruments"))
      (libsource (lib "Firstview") (part "OPA354AQDBVRQ1"))
    )
    (comp (ref "U20")
      (value "OPA354AQDBVRQ1")
      (footprint "SOT-23-5_OPA354A-Q1")
      (description "IC, OpAmp, 250MHz, R-R I/O, SOT-23-5")
      (fields (field (name "MANUFACTURER") "Texas Instruments"))
      (libsource (lib "Firstview") (part "OPA354AQDBVRQ1"))
    )
    (comp (ref "U22")
      (value "OPA354AQDBVRQ1")
      (footprint "SOT-23-5_OPA354A-Q1")
      (description "IC, OpAmp, 250MHz, R-R I/O, SOT-23-5")
      (fields (field (name "MANUFACTURER") "Texas Instruments"))
      (libsource (lib "Firstview") (part "OPA354AQDBVRQ1"))
    )
    (comp (ref "U23")
      (value "OPA354AQDBVRQ1")
      (footprint "SOT-23-5_OPA354A-Q1")
      (description "IC, OpAmp, 250MHz, R-R I/O, SOT-23-5")
      (fields (field (name "MANUFACTURER") "Texas Instruments"))
      (libsource (lib "Firstview") (part "OPA354AQDBVRQ1"))
    )
    (comp (ref "U32")
      (value "MFI337S3959")
      (footprint "CP8PMFI-MFI337S3959")
      (description "IC, Apple Authentication Coprocessor, 2.0C, 8USON")
      (fields (field (name "DNP") "DNP") (field (name "MANUFACTURER") "Apple"))
      (libsource (lib "Firstview") (part "MFI337S3959"))
    )
    (comp (ref "Y3")
      (value "32MHz")
      (footprint "DFN(3.2x2.5)_CX3225SB32000D0FPLCC")
      (description "Clock, Crystal, 32MHz, 20ppm, 8pF, SMD")
      (fields
        (field (name "MANUFACTURER") "AVX Corp/Kyocera Corp")
        (field (name "Comment") "CX3225SB32000D0FPLCC")
      )
      (libsource (lib "Firstview") (part "CX3225SB32000D0FPLCC"))
    )
  )
  (nets
    (net (code "1") (name "/APP_I2C_CLK") (class "Default")
      (node (ref "R148") (pin "1") (pinfunction "1_1") (pintype "passive"))
      (node (ref "U10") (pin "19") (pinfunction "SCL_19") (pintype "bidirectional"))
      (node (ref "U32") (pin "6") (pinfunction "SCL_6") (pintype "input"))
    )
    (net (code "2") (name "/APP_I2C_DATA") (class "Default")
      (node (ref "R145") (pin "1") (pinfunction "1_1") (pintype "passive"))
      (node (ref "U10") (pin "20") (pinfunction "SDA_20") (pintype "bidirectional"))
      (node (ref "U32") (pin "2") (pinfunction "SDA_2") (pintype "bidirectional"))
    )
    (net (code "3") (name "/APP_RESET") (class "Default")
      (node (ref "U32") (pin "7") (pinfunction "RST_7") (pintype "input"))
    )
    (net (code "4") (name "/CAM1_AN") (class "Default")
      (node (ref "C211") (pin "2") (pinfunction "2_2") (pintype "passive"))
      (node (ref "C231") (pin "1") (pinfunction "1_1") (pintype "passive"))
      (node (ref "R123") (pin "2") (pinfunction "2_2") (pintype "passive"))
      (node (ref "R129") (pin "1") (pinfunction "1_1") (pintype "passive"))
      (node (ref "U18") (pin "1") (pinfunction "OUT_1") (pintype "output"))
    )
    (net (code "5") (name "/CAM1_N") (class "Default")
      (node (ref "C207") (pin "1") (pinfunction "1_1") (pintype "passive"))
    )
    (net (code "6") (name "/CAM1_P") (class "Default")
      (node (ref "C203") (pin "1") (pinfunction "1_1") (pintype "passive"))
    )
    (net (code "7") (name "/CAM2_AN") (class "Default")
      (node (ref "C212") (pin "2") (pinfunction "2_2") (pintype "passive"))
      (node (ref "C232") (pin "1") (pinfunction "1_1") (pintype "passive"))
      (node (ref "R124") (pin "2") (pinfunction "2_2") (pintype "passive"))
      (node (ref "R136") (pin "1") (pinfunction "1_1") (pintype "passive"))
      (node (ref "U20") (pin "1") (pinfunction "OUT_1") (pintype "output"))
    )
    (net (code "8") (name "/CAM2_N") (class "Default")
      (node (ref "C208") (pin "1") (pinfunction "1_1") (pintype "passive"))
    )
    (net (code "9") (name "/CAM2_P") (class "Default")
      (node (ref "C204") (pin "1") (pinfunction "1_1") (pintype "passive"))
    )
    (net (code "10") (name "/CAM3_AN") (class "Default")
      (node (ref "C213") (pin "2") (pinfunction "2_2") (pintype "passive"))
      (node (ref "C237") (pin "1") (pinfunction "1_1") (pintype "passive"))
      (node (ref "R125") (pin "2") (pinfunction "2_2") (pintype "passive"))
      (node (ref "R140") (pin "1") (pinfunction "1_1") (pintype "passive"))
      (node (ref "U22") (pin "1") (pinfunction "OUT_1") (pintype "output"))
    )
    (net (code "11") (name "/CAM3_N") (class "Default")
      (node (ref "C209") (pin "1") (pinfunction "1_1") (pintype "passive"))
    )
    (net (code "12") (name "/CAM3_P") (class "Default")
      (node (ref "C205") (pin "1") (pinfunction "1_1") (pintype "passive"))
    )
    (net (code "13") (name "/CAM4_AN") (class "Default")
      (node (ref "C214") (pin "2") (pinfunction "2_2") (pintype "passive"))
      (node (ref "C238") (pin "1") (pinfunction "1_1") (pintype "passive"))
      (node (ref "R126") (pin "2") (pinfunction "2_2") (pintype "passive"))
      (node (ref "R144") (pin "1") (pinfunction "1_1") (pintype "passive"))
      (node (ref "U23") (pin "1") (pinfunction "OUT_1") (pintype "output"))
    )
    (net (code "14") (name "/CAM4_N") (class "Default")
      (node (ref "C210") (pin "1") (pinfunction "1_1") (pintype "passive"))
    )
    (net (code "15") (name "/CAM4_P") (class "Default")
      (node (ref "C206") (pin "1") (pinfunction "1_1") (pintype "passive"))
    )
    (net (code "16") (name "/CAM_APP_I2C_CLK") (class "Default")
      (node (ref "R141") (pin "2") (pinfunction "2_2") (pintype "passive"))
      (node (ref "R148") (pin "2") (pinfunction "2_2") (pintype "passive"))
    )
    (net (code "17") (name "/CAM_APP_I2C_DATA") (class "Default")
      (node (ref "R142") (pin "2") (pinfunction "2_2") (pintype "passive"))
      (node (ref "R145") (pin "2") (pinfunction "2_2") (pintype "passive"))
    )
    (net (code "18") (name "/CAM_CLK") (class "Default")
      (node (ref "R139") (pin "2") (pinfunction "2_2") (pintype "passive"))
    )
    (net (code "19") (name "/CAM_DATA_A0") (class "Default")
      (node (ref "R127") (pin "2") (pinfunction "2_2") (pintype "passive"))
    )
    (net (code "20") (name "/CAM_DATA_A1") (class "Default")
      (node (ref "R128") (pin "2") (pinfunction "2_2") (pintype "passive"))
    )
    (net (code "21") (name "/CAM_DATA_A2") (class "Default")
      (node (ref "R130") (pin "2") (pinfunction "2_2") (pintype "passive"))
    )
    (net (code "22") (name "/CAM_DATA_A3") (class "Default")
      (node (ref "R131") (pin "2") (pinfunction "2_2") (pintype "passive"))
    )
    (net (code "23") (name "/CAM_DATA_A4") (class "Default")
      (node (ref "R132") (pin "2") (pinfunction "2_2") (pintype "passive"))
    )
    (net (code "24") (name "/CAM_DATA_A5") (class "Default")
      (node (ref "R133") (pin "2") (pinfunction "2_2") (pintype "passive"))
    )
    (net (code "25") (name "/CAM_DATA_A6") (class "Default")
      (node (ref "R134") (pin "2") (pinfunction "2_2") (pintype "passive"))
    )
    (net (code "26") (name "/CAM_DATA_A7") (class "Default")
      (node (ref "R135") (pin "2") (pinfunction "2_2") (pintype "passive"))
    )
    (net (code "27") (name "/CAM_EN") (class "Default")
      (node (ref "R143") (pin "2") (pinfunction "2_2") (pintype "passive"))
      (node (ref "U10") (pin "14") (pinfunction "SLEEP_14") (pintype "input"))
    )
    (net (code "28") (name "/CAM_HSYNC") (class "Default")
      (node (ref "R137") (pin "2") (pinfunction "2_2") (pintype "passive"))
    )
    (net (code "29") (name "/CAM_VSYNC") (class "Default")
      (node (ref "R138") (pin "2") (pinfunction "2_2") (pintype "passive"))
    )
    (net (code "30") (name "/VID_ENC_RST_N") (class "Default")
      (node (ref "C240") (pin "1") (pinfunction "1_1") (pintype "passive"))
      (node (ref "R147") (pin "1") (pinfunction "1_1") (pintype "passive"))
      (node (ref "U10") (pin "15") (pinfunction "RESET_L_15") (pintype "input"))
    )
    (net (code "31") (name "1V5SW") (class "Default")
      (node (ref "C222") (pin "1") (pinfunction "1_1") (pintype "passive"))
      (node (ref "C230") (pin "1") (pinfunction "1_1") (pintype "passive"))
      (node (ref "FB5") (pin "2") (pinfunction "2_2") (pintype "passive"))
      (node (ref "FB7") (pin "2") (pinfunction "2_2") (pintype "passive"))
    )
    (net (code "32") (name "3V3SW") (class "Default")
      (node (ref "C215") (pin "1") (pinfunction "1_1") (pintype "passive"))
      (node (ref "C223") (pin "1") (pinfunction "1_1") (pintype "passive"))
      (node (ref "C340") (pin "1") (pinfunction "1_1") (pintype "passive"))
      (node (ref "FB4") (pin "1") (pinfunction "1_1") (pintype "passive"))
      (node (ref "FB6") (pin "1") (pinfunction "1_1") (pintype "passive"))
      (node (ref "R141") (pin "1") (pinfunction "1_1") (pintype "passive"))
      (node (ref "R142") (pin "1") (pinfunction "1_1") (pintype "passive"))
      (node (ref "R143") (pin "1") (pinfunction "1_1") (pintype "passive"))
      (node (ref "U32") (pin "8") (pinfunction "VCC_8") (pintype "passive"))
    )
    (net (code "33") (name "5VSW") (class "Default")
      (node (ref "C199") (pin "1") (pinfunction "1_1") (pintype "passive"))
      (node (ref "C200") (pin "1") (pinfunction "1_1") (pintype "passive"))
      (node (ref "C201") (pin "1") (pinfunction "1_1") (pintype "passive"))
      (node (ref "C202") (pin "1") (pinfunction "1_1") (pintype "passive"))
      (node (ref "R95") (pin "1") (pinfunction "1_1") (pintype "passive"))
      (node (ref "R96") (pin "1") (pinfunction "1_1") (pintype "passive"))
      (node (ref "R97") (pin "1") (pinfunction "1_1") (pintype "passive"))
      (node (ref "R98") (pin "1") (pinfunction "1_1") (pintype "passive"))
      (node (ref "U18") (pin "5") (pinfunction "V+_5") (pintype "power_in"))
      (node (ref "U20") (pin "5") (pinfunction "V+_5") (pintype "power_in"))
      (node (ref "U22") (pin "5") (pinfunction "V+_5") (pintype "power_in"))
      (node (ref "U23") (pin "5") (pinfunction "V+_5") (pintype "power_in"))
    )
    (net (code "34") (name "GND") (class "Default")
      (node (ref "C191") (pin "2") (pinfunction "2_2") (pintype "passive"))
      (node (ref "C193") (pin "2") (pinfunction "2_2") (pintype "passive"))
      (node (ref "C195") (pin "2") (pinfunction "2_2") (pintype "passive"))
      (node (ref "C197") (pin "2") (pinfunction "2_2") (pintype "passive"))
      (node (ref "C199") (pin "2") (pinfunction "2_2") (pintype "passive"))
      (node (ref "C200") (pin "2") (pinfunction "2_2") (pintype "passive"))
      (node (ref "C201") (pin "2") (pinfunction "2_2") (pintype "passive"))
      (node (ref "C202") (pin "2") (pinfunction "2_2") (pintype "passive"))
      (node (ref "C215") (pin "2") (pinfunction "2_2") (pintype "passive"))
      (node (ref "C216") (pin "2") (pinfunction "2_2") (pintype "passive"))
      (node (ref "C217") (pin "2") (pinfunction "2_2") (pintype "passive"))
      (node (ref "C218") (pin "2") (pinfunction "2_2") (pintype "passive"))
      (node (ref "C219") (pin "2") (pinfunction "2_2") (pintype "passive"))
      (node (ref "C220") (pin "2") (pinfunction "2_2") (pintype "passive"))
      (node (ref "C221") (pin "2") (pinfunction "2_2") (pintype "passive"))
      (node (ref "C222") (pin "2") (pinfunction "2_2") (pintype "passive"))
      (node (ref "C223") (pin "2") (pinfunction "2_2") (pintype "passive"))
      (node (ref "C224") (pin "2") (pinfunction "2_2") (pintype "passive"))
      (node (ref "C225") (pin "2") (pinfunction "2_2") (pintype "passive"))
      (node (ref "C226") (pin "2") (pinfunction "2_2") (pintype "passive"))
      (node (ref "C227") (pin "2") (pinfunction "2_2") (pintype "passive"))
      (node (ref "C228") (pin "2") (pinfunction "2_2") (pintype "passive"))
      (node (ref "C229") (pin "2") (pinfunction "2_2") (pintype "passive"))
      (node (ref "C230") (pin "2") (pinfunction "2_2") (pintype "passive"))
      (node (ref "C234") (pin "2") (pinfunction "2_2") (pintype "passive"))
      (node (ref "C235") (pin "2") (pinfunction "2_2") (pintype "passive"))
      (node (ref "C236") (pin "2") (pinfunction "2_2") (pintype "passive"))
      (node (ref "C239") (pin "1") (pinfunction "1_1") (pintype "passive"))
      (node (ref "C240") (pin "2") (pinfunction "2_2") (pintype "passive"))
      (node (ref "C241") (pin "1") (pinfunction "1_1") (pintype "passive"))
      (node (ref "C340") (pin "2") (pinfunction "2_2") (pintype "passive"))
      (node (ref "R101") (pin "1") (pinfunction "1_1") (pintype "passive"))
      (node (ref "R103") (pin "1") (pinfunction "1_1") (pintype "passive"))
      (node (ref "R105") (pin "1") (pinfunction "1_1") (pintype "passive"))
      (node (ref "R111") (pin "2") (pinfunction "2_2") (pintype "passive"))
      (node (ref "R112") (pin "2") (pinfunction "2_2") (pintype "passive"))
      (node (ref "R113") (pin "2") (pinfunction "2_2") (pintype "passive"))
      (node (ref "R114") (pin "2") (pinfunction "2_2") (pintype "passive"))
      (node (ref "R119") (pin "2") (pinfunction "2_2") (pintype "passive"))
      (node (ref "R120") (pin "2") (pinfunction "2_2") (pintype "passive"))
      (node (ref "R121") (pin "2") (pinfunction "2_2") (pintype "passive"))
      (node (ref "R122") (pin "2") (pinfunction "2_2") (pintype "passive"))
      (node (ref "R129") (pin "2") (pinfunction "2_2") (pintype "passive"))
      (node (ref "R136") (pin "2") (pinfunction "2_2") (pintype "passive"))
      (node (ref "R140") (pin "2") (pinfunction "2_2") (pintype "passive"))
      (node (ref "R144") (pin "2") (pinfunction "2_2") (pintype "passive"))
      (node (ref "R147") (pin "2") (pinfunction "2_2") (pintype "passive"))
      (node (ref "R99") (pin "1") (pinfunction "1_1") (pintype "passive"))
      (node (ref "U10") (pin "1") (pinfunction "AGND_1") (pintype "power_in"))
      (node (ref "U10") (pin "13") (pinfunction "TEST_13") (pintype "input"))
      (node (ref "U10") (pin "16") (pinfunction "DGND_16") (pintype "power_in"))
      (node (ref "U10") (pin "18") (pinfunction "SAS_18") (pintype "input"))
      (node (ref "U10") (pin "21") (pinfunction "DGND_21") (pintype "power_in"))
      (node (ref "U10") (pin "34") (pinfunction "DGND_34") (pintype "power_in"))
      (node (ref "U10") (pin "43") (pinfunction "DGND_43") (pintype "power_in"))
      (node (ref "U10") (pin "44") (pinfunction "INS1_44") (pintype "input"))
      (node (ref "U10") (pin "45") (pinfunction "INS2_45") (pintype "input"))
      (node (ref "U10") (pin "46") (pinfunction "INS3_46") (pintype "input"))
      (node (ref "U10") (pin "48") (pinfunction "PGND_48") (pintype "power_in"))
      (node (ref "U10") (pin "7") (pinfunction "AGND_7") (pintype "power_in"))
      (node (ref "U18") (pin "2") (pinfunction "V-_2") (pintype "power_in"))
      (node (ref "U20") (pin "2") (pinfunction "V-_2") (pintype "power_in"))
      (node (ref "U22") (pin "2") (pinfunction "V-_2") (pintype "power_in"))
      (node (ref "U23") (pin "2") (pinfunction "V-_2") (pintype "power_in"))
      (node (ref "U32") (pin "1") (pinfunction "GND_1") (pintype "passive"))
      (node (ref "U32") (pin "EP") (pinfunction "EP_EP") (pintype "passive"))
      (node (ref "Y3") (pin "2") (pintype "passive"))
      (node (ref "Y3") (pin "4") (pintype "passive"))
    )
    (net (code "35") (name "Net-(C191-Pad1)") (class "Default")
      (node (ref "C191") (pin "1") (pinfunction "1_1") (pintype "passive"))
      (node (ref "C192") (pin "2") (pinfunction "2_2") (pintype "passive"))
      (node (ref "R100") (pin "1") (pinfunction "1_1") (pintype "passive"))
      (node (ref "R95") (pin "2") (pinfunction "2_2") (pintype "passive"))
      (node (ref "R99") (pin "2") (pinfunction "2_2") (pintype "passive"))
    )
    (net (code "36") (name "Net-(C193-Pad1)") (class "Default")
      (node (ref "C193") (pin "1") (pinfunction "1_1") (pintype "passive"))
      (node (ref "C194") (pin "2") (pinfunction "2_2") (pintype "passive"))
      (node (ref "R101") (pin "2") (pinfunction "2_2") (pintype "passive"))
      (node (ref "R102") (pin "1") (pinfunction "1_1") (pintype "passive"))
      (node (ref "R96") (pin "2") (pinfunction "2_2") (pintype "passive"))
    )
    (net (code "37") (name "Net-(C195-Pad1)") (class "Default")
      (node (ref "C195") (pin "1") (pinfunction "1_1") (pintype "passive"))
      (node (ref "C196") (pin "2") (pinfunction "2_2") (pintype "passive"))
      (node (ref "R103") (pin "2") (pinfunction "2_2") (pintype "passive"))
      (node (ref "R104") (pin "1") (pinfunction "1_1") (pintype "passive"))
      (node (ref "R97") (pin "2") (pinfunction "2_2") (pintype "passive"))
    )
    (net (code "38") (name "Net-(C197-Pad1)") (class "Default")
      (node (ref "C197") (pin "1") (pinfunction "1_1") (pintype "passive"))
      (node (ref "C198") (pin "2") (pinfunction "2_2") (pintype "passive"))
      (node (ref "R105") (pin "2") (pinfunction "2_2") (pintype "passive"))
      (node (ref "R106") (pin "1") (pinfunction "1_1") (pintype "passive"))
      (node (ref "R98") (pin "2") (pinfunction "2_2") (pintype "passive"))
    )
    (net (code "39") (name "Net-(C203-Pad2)") (class "Default")
      (node (ref "C203") (pin "2") (pinfunction "2_2") (pintype "passive"))
      (node (ref "R107") (pin "2") (pinfunction "2_2") (pintype "passive"))
      (node (ref "R111") (pin "1") (pinfunction "1_1") (pintype "passive"))
    )
    (net (code "40") (name "Net-(C204-Pad2)") (class "Default")
      (node (ref "C204") (pin "2") (pinfunction "2_2") (pintype "passive"))
      (node (ref "R108") (pin "2") (pinfunction "2_2") (pintype "passive"))
      (node (ref "R112") (pin "1") (pinfunction "1_1") (pintype "passive"))
    )
    (net (code "41") (name "Net-(C205-Pad2)") (class "Default")
      (node (ref "C205") (pin "2") (pinfunction "2_2") (pintype "passive"))
      (node (ref "R109") (pin "2") (pinfunction "2_2") (pintype "passive"))
      (node (ref "R113") (pin "1") (pinfunction "1_1") (pintype "passive"))
    )
    (net (code "42") (name "Net-(C206-Pad2)") (class "Default")
      (node (ref "C206") (pin "2") (pinfunction "2_2") (pintype "passive"))
      (node (ref "R110") (pin "2") (pinfunction "2_2") (pintype "passive"))
      (node (ref "R114") (pin "1") (pinfunction "1_1") (pintype "passive"))
    )
    (net (code "43") (name "Net-(C207-Pad2)") (class "Default")
      (node (ref "C207") (pin "2") (pinfunction "2_2") (pintype "passive"))
      (node (ref "R115") (pin "1") (pinfunction "1_1") (pintype "passive"))
      (node (ref "R119") (pin "1") (pinfunction "1_1") (pintype "passive"))
    )
    (net (code "44") (name "Net-(C208-Pad2)") (class "Default")
      (node (ref "C208") (pin "2") (pinfunction "2_2") (pintype "passive"))
      (node (ref "R116") (pin "1") (pinfunction "1_1") (pintype "passive"))
      (node (ref "R120") (pin "1") (pinfunction "1_1") (pintype "passive"))
    )
    (net (code "45") (name "Net-(C209-Pad2)") (class "Default")
      (node (ref "C209") (pin "2") (pinfunction "2_2") (pintype "passive"))
      (node (ref "R117") (pin "1") (pinfunction "1_1") (pintype "passive"))
      (node (ref "R121") (pin "1") (pinfunction "1_1") (pintype "passive"))
    )
    (net (code "46") (name "Net-(C210-Pad2)") (class "Default")
      (node (ref "C210") (pin "2") (pinfunction "2_2") (pintype "passive"))
      (node (ref "R118") (pin "1") (pinfunction "1_1") (pintype "passive"))
      (node (ref "R122") (pin "1") (pinfunction "1_1") (pintype "passive"))
    )
    (net (code "47") (name "Net-(C216-Pad1)") (class "Default")
      (node (ref "C216") (pin "1") (pinfunction "1_1") (pintype "passive"))
      (node (ref "C217") (pin "1") (pinfunction "1_1") (pintype "passive"))
      (node (ref "C218") (pin "1") (pinfunction "1_1") (pintype "passive"))
      (node (ref "FB4") (pin "2") (pinfunction "2_2") (pintype "passive"))
      (node (ref "U10") (pin "12") (pinfunction "AVDD_12") (pintype "power_in"))
      (node (ref "U10") (pin "5") (pinfunction "AVDD_5") (pintype "power_in"))
    )
    (net (code "48") (name "Net-(C219-Pad1)") (class "Default")
      (node (ref "C219") (pin "1") (pinfunction "1_1") (pintype "passive"))
      (node (ref "C220") (pin "1") (pinfunction "1_1") (pintype "passive"))
      (node (ref "C221") (pin "1") (pinfunction "1_1") (pintype "passive"))
      (node (ref "FB5") (pin "1") (pinfunction "1_1") (pintype "passive"))
      (node (ref "U10") (pin "17") (pinfunction "DVDDCO_17") (pintype "power_in"))
      (node (ref "U10") (pin "36") (pinfunction "DVDDCO_36") (pintype "power_in"))
    )
    (net (code "49") (name "Net-(C224-Pad1)") (class "Default")
      (node (ref "C224") (pin "1") (pinfunction "1_1") (pintype "passive"))
      (node (ref "C225") (pin "1") (pinfunction "1_1") (pintype "passive"))
      (node (ref "C226") (pin "1") (pinfunction "1_1") (pintype "passive"))
      (node (ref "C227") (pin "1") (pinfunction "1_1") (pintype "passive"))
      (node (ref "FB6") (pin "2") (pinfunction "2_2") (pintype "passive"))
      (node (ref "U10") (pin "24") (pinfunction "DVDDIO_24") (pintype "power_in"))
      (node (ref "U10") (pin "29") (pinfunction "DVDDIO_29") (pintype "power_in"))
      (node (ref "U10") (pin "42") (pinfunction "DVDDIO_42") (pintype "power_in"))
    )
    (net (code "50") (name "Net-(U10-CLKX20)") (class "Default")
      (node (ref "R139") (pin "1") (pinfunction "1_1") (pintype "passive"))
      (node (ref "U10") (pin "35") (pinfunction "CLKX20_35") (pintype "output"))
    )
    (net (code "51") (name "Net-(U10-HSYNC_L)") (class "Default")
      (node (ref "R137") (pin "1") (pinfunction "1_1") (pintype "passive"))
      (node (ref "U10") (pin "37") (pinfunction "HSYNC_L_37") (pintype "output"))
    )
    (net (code "52") (name "Net-(U10-PVDD)") (class "Default")
      (node (ref "C228") (pin "1") (pinfunction "1_1") (pintype "passive"))
      (node (ref "C229") (pin "1") (pinfunction "1_1") (pintype "passive"))
      (node (ref "FB7") (pin "1") (pinfunction "1_1") (pintype "passive"))
      (node (ref "U10") (pin "47") (pinfunction "PVDD_47") (pintype "power_in"))
    )
    (net (code "53") (name "Net-(U10-REF)") (class "Default")
      (node (ref "C236") (pin "1") (pinfunction "1_1") (pintype "passive"))
      (node (ref "U10") (pin "2") (pinfunction "REF_2") (pintype "power_in"))
    )
    (net (code "54") (name "Net-(U10-REFN)") (class "Default")
      (node (ref "C233") (pin "2") (pinfunction "2_2") (pintype "passive"))
      (node (ref "C235") (pin "1") (pinfunction "1_1") (pintype "passive"))
      (node (ref "U10") (pin "4") (pinfunction "REFN_4") (pintype "power_in"))
    )
    (net (code "55") (name "Net-(U10-REFP)") (class "Default")
      (node (ref "C233") (pin "1") (pinfunction "1_1") (pintype "passive"))
      (node (ref "C234") (pin "1") (pinfunction "1_1") (pintype "passive"))
      (node (ref "U10") (pin "3") (pinfunction "REFP_3") (pintype "power_in"))
    )
    (net (code "56") (name "Net-(U10-VIN1)") (class "Default")
      (node (ref "C231") (pin "2") (pinfunction "2_2") (pintype "passive"))
      (node (ref "U10") (pin "8") (pinfunction "VIN1_8") (pintype "input"))
    )
    (net (code "57") (name "Net-(U10-VIN2)") (class "Default")
      (node (ref "C232") (pin "2") (pinfunction "2_2") (pintype "passive"))
      (node (ref "U10") (pin "9") (pinfunction "VIN2_9") (pintype "input"))
    )
    (net (code "58") (name "Net-(U10-VIN3)") (class "Default")
      (node (ref "C237") (pin "2") (pinfunction "2_2") (pintype "passive"))
      (node (ref "U10") (pin "10") (pinfunction "VIN3_10") (pintype "input"))
    )
    (net (code "59") (name "Net-(U10-VIN4)") (class "Default")
      (node (ref "C238") (pin "2") (pinfunction "2_2") (pintype "passive"))
      (node (ref "U10") (pin "11") (pinfunction "VIN4_11") (pintype "input"))
    )
    (net (code "60") (name "Net-(U10-VSYNC_L)") (class "Default")
      (node (ref "R138") (pin "1") (pinfunction "1_1") (pintype "passive"))
      (node (ref "U10") (pin "38") (pinfunction "VSYNC_L_38") (pintype "output"))
    )
    (net (code "61") (name "Net-(U10-XI)") (class "Default")
      (node (ref "C239") (pin "2") (pinfunction "2_2") (pintype "passive"))
      (node (ref "R146") (pin "1") (pinfunction "1_1") (pintype "passive"))
      (node (ref "U10") (pin "23") (pinfunction "XI_23") (pintype "input"))
      (node (ref "Y3") (pin "3") (pinfunction "OSC2_3") (pintype "passive"))
    )
    (net (code "62") (name "Net-(U10-XO)") (class "Default")
      (node (ref "R146") (pin "2") (pinfunction "2_2") (pintype "passive"))
      (node (ref "R149") (pin "2") (pinfunction "2_2") (pintype "passive"))
      (node (ref "U10") (pin "22") (pinfunction "XO_22") (pintype "output"))
    )
    (net (code "63") (name "Net-(U10-Y0)") (class "Default")
      (node (ref "R127") (pin "1") (pinfunction "1_1") (pintype "passive"))
      (node (ref "U10") (pin "25") (pinfunction "Y0_25") (pintype "output"))
    )
    (net (code "64") (name "Net-(U10-Y1)") (class "Default")
      (node (ref "R128") (pin "1") (pinfunction "1_1") (pintype "passive"))
      (node (ref "U10") (pin "26") (pinfunction "Y1_26") (pintype "output"))
    )
    (net (code "65") (name "Net-(U10-Y2)") (class "Default")
      (node (ref "R130") (pin "1") (pinfunction "1_1") (pintype "passive"))
      (node (ref "U10") (pin "27") (pinfunction "Y2_27") (pintype "output"))
    )
    (net (code "66") (name "Net-(U10-Y3)") (class "Default")
      (node (ref "R131") (pin "1") (pinfunction "1_1") (pintype "passive"))
      (node (ref "U10") (pin "28") (pinfunction "Y3_28") (pintype "output"))
    )
    (net (code "67") (name "Net-(U10-Y4)") (class "Default")
      (node (ref "R132") (pin "1") (pinfunction "1_1") (pintype "passive"))
      (node (ref "U10") (pin "30") (pinfunction "Y4_30") (pintype "output"))
    )
    (net (code "68") (name "Net-(U10-Y5)") (class "Default")
      (node (ref "R133") (pin "1") (pinfunction "1_1") (pintype "passive"))
      (node (ref "U10") (pin "31") (pinfunction "Y5_31") (pintype "output"))
    )
    (net (code "69") (name "Net-(U10-Y6)") (class "Default")
      (node (ref "R134") (pin "1") (pinfunction "1_1") (pintype "passive"))
      (node (ref "U10") (pin "32") (pinfunction "Y6_32") (pintype "output"))
    )
    (net (code "70") (name "Net-(U10-Y7)") (class "Default")
      (node (ref "R135") (pin "1") (pinfunction "1_1") (pintype "passive"))
      (node (ref "U10") (pin "33") (pinfunction "Y7_33") (pintype "output"))
    )
    (net (code "71") (name "Net-(U18-IN+)") (class "Default")
      (node (ref "C192") (pin "1") (pinfunction "1_1") (pintype "passive"))
      (node (ref "R100") (pin "2") (pinfunction "2_2") (pintype "passive"))
      (node (ref "R107") (pin "1") (pinfunction "1_1") (pintype "passive"))
      (node (ref "U18") (pin "3") (pinfunction "IN+_3") (pintype "input"))
    )
    (net (code "72") (name "Net-(U18-IN-)") (class "Default")
      (node (ref "C211") (pin "1") (pinfunction "1_1") (pintype "passive"))
      (node (ref "R115") (pin "2") (pinfunction "2_2") (pintype "passive"))
      (node (ref "R123") (pin "1") (pinfunction "1_1") (pintype "passive"))
      (node (ref "U18") (pin "4") (pinfunction "IN-_4") (pintype "input"))
    )
    (net (code "73") (name "Net-(U20-IN+)") (class "Default")
      (node (ref "C194") (pin "1") (pinfunction "1_1") (pintype "passive"))
      (node (ref "R102") (pin "2") (pinfunction "2_2") (pintype "passive"))
      (node (ref "R108") (pin "1") (pinfunction "1_1") (pintype "passive"))
      (node (ref "U20") (pin "3") (pinfunction "IN+_3") (pintype "input"))
    )
    (net (code "74") (name "Net-(U20-IN-)") (class "Default")
      (node (ref "C212") (pin "1") (pinfunction "1_1") (pintype "passive"))
      (node (ref "R116") (pin "2") (pinfunction "2_2") (pintype "passive"))
      (node (ref "R124") (pin "1") (pinfunction "1_1") (pintype "passive"))
      (node (ref "U20") (pin "4") (pinfunction "IN-_4") (pintype "input"))
    )
    (net (code "75") (name "Net-(U22-IN+)") (class "Default")
      (node (ref "C196") (pin "1") (pinfunction "1_1") (pintype "passive"))
      (node (ref "R104") (pin "2") (pinfunction "2_2") (pintype "passive"))
      (node (ref "R109") (pin "1") (pinfunction "1_1") (pintype "passive"))
      (node (ref "U22") (pin "3") (pinfunction "IN+_3") (pintype "input"))
    )
    (net (code "76") (name "Net-(U22-IN-)") (class "Default")
      (node (ref "C213") (pin "1") (pinfunction "1_1") (pintype "passive"))
      (node (ref "R117") (pin "2") (pinfunction "2_2") (pintype "passive"))
      (node (ref "R125") (pin "1") (pinfunction "1_1") (pintype "passive"))
      (node (ref "U22") (pin "4") (pinfunction "IN-_4") (pintype "input"))
    )
    (net (code "77") (name "Net-(U23-IN+)") (class "Default")
      (node (ref "C198") (pin "1") (pinfunction "1_1") (pintype "passive"))
      (node (ref "R106") (pin "2") (pinfunction "2_2") (pintype "passive"))
      (node (ref "R110") (pin "1") (pinfunction "1_1") (pintype "passive"))
      (node (ref "U23") (pin "3") (pinfunction "IN+_3") (pintype "input"))
    )
    (net (code "78") (name "Net-(U23-IN-)") (class "Default")
      (node (ref "C214") (pin "1") (pinfunction "1_1") (pintype "passive"))
      (node (ref "R118") (pin "2") (pinfunction "2_2") (pintype "passive"))
      (node (ref "R126") (pin "1") (pinfunction "1_1") (pintype "passive"))
      (node (ref "U23") (pin "4") (pinfunction "IN-_4") (pintype "input"))
    )
    (net (code "79") (name "Net-(Y3-OSC1)") (class "Default")
      (node (ref "C241") (pin "2") (pinfunction "2_2") (pintype "passive"))
      (node (ref "R149") (pin "1") (pinfunction "1_1") (pintype "passive"))
      (node (ref "Y3") (pin "1") (pinfunction "OSC1_1") (pintype "passive"))
    )
    (net (code "80") (name "unconnected-(U10-LPFOUTB-Pad6)") (class "Default")
      (node (ref "U10") (pin "6") (pinfunction "LPFOUTB_6") (pintype "output+no_connect"))
    )
    (net (code "81") (name "unconnected-(U10-STATUS1-Pad39)") (class "Default")
      (node (ref "U10") (pin "39") (pinfunction "STATUS1_39") (pintype "output+no_connect"))
    )
    (net (code "82") (name "unconnected-(U10-STATUS2-Pad40)") (class "Default")
      (node (ref "U10") (pin "40") (pinfunction "STATUS2_40") (pintype "output+no_connect"))
    )
    (net (code "83") (name "unconnected-(U10-STATUS3-Pad41)") (class "Default")
      (node (ref "U10") (pin "41") (pinfunction "STATUS3_41") (pintype "output+no_connect"))
    )
  )
)
